# rs232_pic.net
KiCad netlist of a schematic drawn in Altium Designer
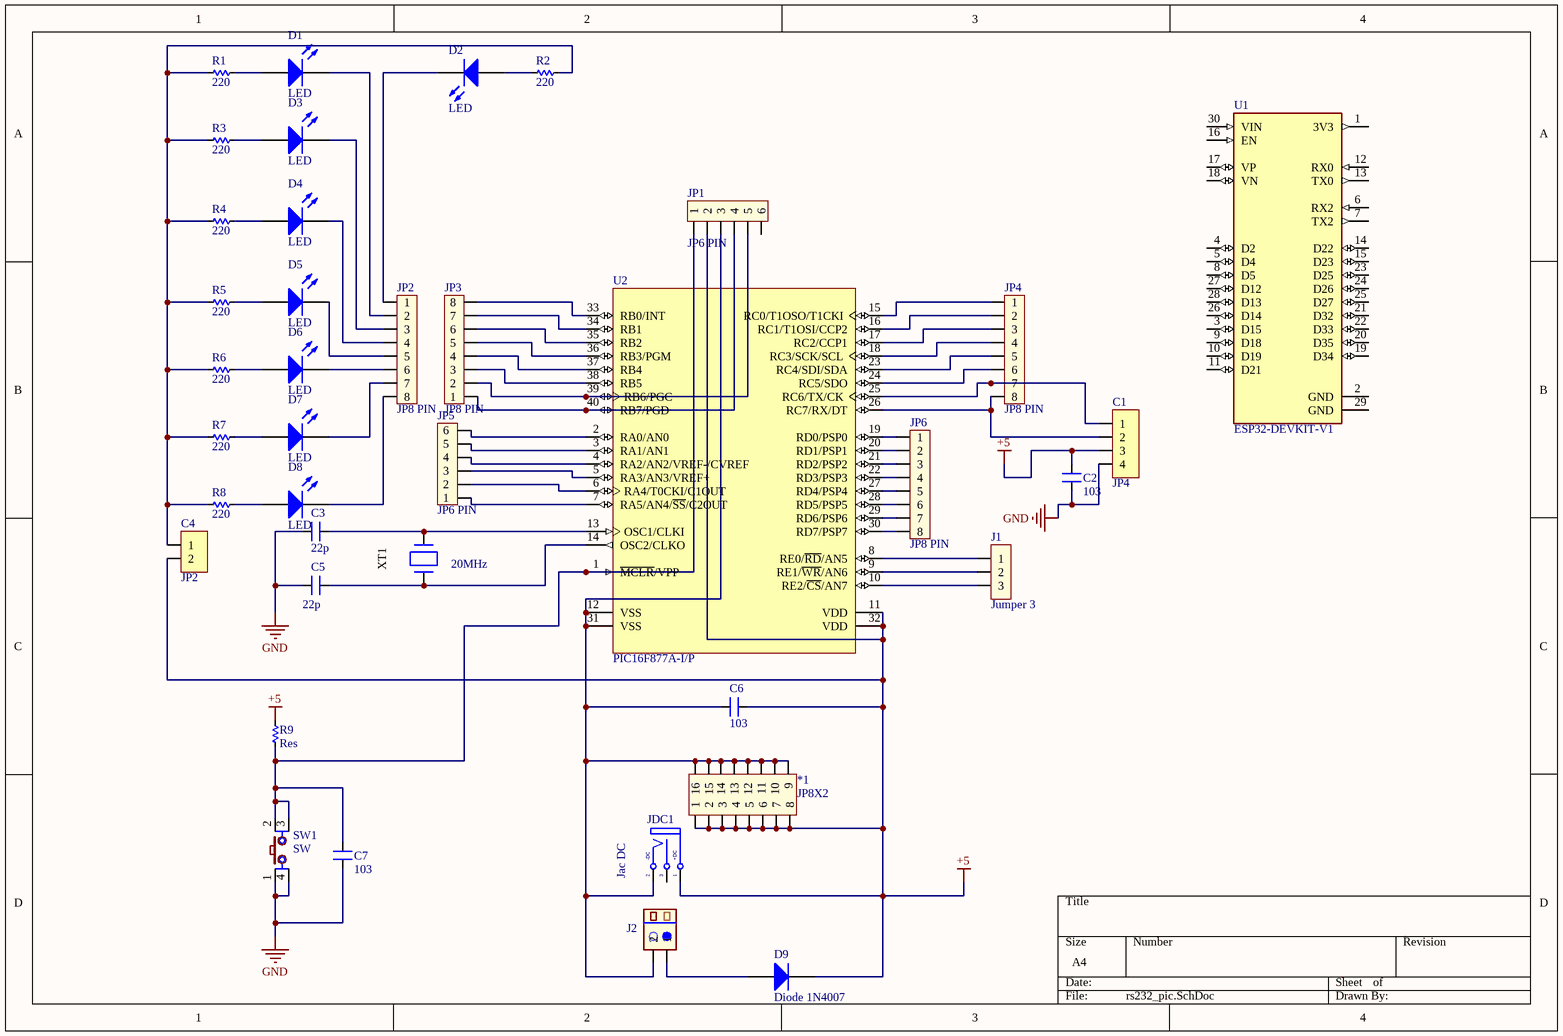
[diagram p0: rs232_pic.SchDoc]

(export (version "E")
  (design (tool "Eeschema 10.0.6"))
  (components
    (comp (ref "*1") (value "JP8X2") (footprint "JP8X2") (libsource (lib "syhaunguyen") (part "JP8X2")))
    (comp (ref "C1")
      (value "JP4")
      (footprint "JP4-C1T")
      (description "WR-PHD 2.54 mm Angled Socket Header")
      (fields
        (field (name "MANUFACTURER") "Würth Elektronik eiSos GmbH")
        (field (name "PARTNO") "613004143121")
        (field (name "CREATED BY") "Karrer Zheng")
      )
      (libsource (lib "LIBRARY1") (part "JP4"))
    )
    (comp (ref "C2")
      (value "103")
      (footprint "CN1.5")
      (description "Cap np 682pF => 104pF")
      (libsource (lib "hphonglib") (part "CN1.5"))
    )
    (comp (ref "C3")
      (value "22p")
      (footprint "CN1.5")
      (description "Cap np 682pF => 104pF")
      (libsource (lib "hphonglib") (part "CN1.5"))
    )
    (comp (ref "C4")
      (value "JP2")
      (footprint "JP2-CLOSED")
      (description "WR-PHD 2.54 mm Angled Socket Header")
      (fields
        (field (name "MANUFACTURER") "Würth Elektronik eiSos GmbH")
        (field (name "PARTNO") "613002143121")
        (field (name "CREATED BY") "Karrer Zheng")
      )
      (libsource (lib "LIBRARY1") (part "JP2"))
    )
    (comp (ref "C5")
      (value "22p")
      (footprint "CN1.5")
      (description "Cap np 682pF => 104pF")
      (libsource (lib "hphonglib") (part "CN1.5"))
    )
    (comp (ref "C6")
      (value "103")
      (footprint "CN1.5")
      (description "Cap np 682pF => 104pF")
      (libsource (lib "hphonglib") (part "CN1.5"))
    )
    (comp (ref "C7")
      (value "103")
      (footprint "CN1.5")
      (description "Cap np 682pF => 104pF")
      (libsource (lib "hphonglib") (part "CN1.5"))
    )
    (comp (ref "D1")
      (value "LED")
      (footprint "LED-0 5mm BLUE")
      (description "Typical LED")
      (fields (field (name "PUBLISHER") "Altium Limited"))
      (libsource (lib "hphonglib") (part "LED"))
    )
    (comp (ref "D2")
      (value "LED")
      (footprint "LED-0 5mm BLUE")
      (description "Typical LED")
      (fields (field (name "PUBLISHER") "Altium Limited"))
      (libsource (lib "hphonglib") (part "LED"))
    )
    (comp (ref "D3")
      (value "LED")
      (footprint "LED-0 5mm BLUE")
      (description "Typical LED")
      (fields (field (name "PUBLISHER") "Altium Limited"))
      (libsource (lib "hphonglib") (part "LED"))
    )
    (comp (ref "D4")
      (value "LED")
      (footprint "LED-0 5mm BLUE")
      (description "Typical LED")
      (fields (field (name "PUBLISHER") "Altium Limited"))
      (libsource (lib "hphonglib") (part "LED"))
    )
    (comp (ref "D5")
      (value "LED")
      (footprint "LED-0 5mm BLUE")
      (description "Typical LED")
      (fields (field (name "PUBLISHER") "Altium Limited"))
      (libsource (lib "hphonglib") (part "LED"))
    )
    (comp (ref "D6")
      (value "LED")
      (footprint "LED-0 5mm BLUE")
      (description "Typical LED")
      (fields (field (name "PUBLISHER") "Altium Limited"))
      (libsource (lib "hphonglib") (part "LED"))
    )
    (comp (ref "D7")
      (value "LED")
      (footprint "LED-0 5mm BLUE")
      (description "Typical LED")
      (fields (field (name "PUBLISHER") "Altium Limited"))
      (libsource (lib "hphonglib") (part "LED"))
    )
    (comp (ref "D8")
      (value "LED")
      (footprint "LED-0 5mm BLUE")
      (description "Typical LED")
      (fields (field (name "PUBLISHER") "Altium Limited"))
      (libsource (lib "hphonglib") (part "LED"))
    )
    (comp (ref "D9")
      (value "Diode 1N4007")
      (footprint "DO-41")
      (description "1 Amp General Purpose Rectifier")
      (fields (field (name "PUBLISHER") "Altium Limited"))
      (libsource (lib "hphonglib") (part "Diode 1N4007"))
    )
    (comp (ref "J1") (value "Jumper 3") (footprint "JP3") (libsource (lib "hphonglib") (part "JP3")))
    (comp (ref "J2")
      (value "CON.Domino2")
      (footprint "Domino 2M")
      (description "2 pins Domino Header")
      (fields (field (name "PUBLISHER") "Hoang Nguyen"))
      (libsource (lib "hphonglib") (part "CON.Domino2"))
    )
    (comp (ref "JDC1")
      (value "Jac DC")
      (footprint "DC0")
      (description "Jac DC input")
      (libsource (lib "LIBRARY1") (part "DCIN"))
    )
    (comp (ref "JP1") (value "JP6 PIN") (footprint "JP6") (libsource (lib "syhaunguyen") (part "JP6")))
    (comp (ref "JP2") (value "JP8 PIN") (footprint "JP8") (libsource (lib "hphonglib") (part "JP8")))
    (comp (ref "JP3") (value "JP8 PIN") (footprint "JP8") (libsource (lib "") (part "JP8_1")))
    (comp (ref "JP4") (value "JP8 PIN") (footprint "JP8") (libsource (lib "hphonglib") (part "JP8")))
    (comp (ref "JP5") (value "JP6 PIN") (footprint "JP6") (libsource (lib "hphonglib") (part "JP6")))
    (comp (ref "JP6") (value "JP8 PIN") (footprint "JP8") (libsource (lib "hphonglib") (part "JP8")))
    (comp (ref "R1")
      (value "220")
      (footprint "RES-1/2W")
      (description "Res")
      (fields
        (field (name "MANUFACTURER") "Generic Components")
        (field (name "PUBLISHER") "Altium Hobart Technology Centre")
      )
      (libsource (lib "LIBRARY1") (part "Res"))
    )
    (comp (ref "R2")
      (value "220")
      (footprint "RES-1/2W")
      (description "Res")
      (fields
        (field (name "MANUFACTURER") "Generic Components")
        (field (name "PUBLISHER") "Altium Hobart Technology Centre")
      )
      (libsource (lib "LIBRARY1") (part "Res"))
    )
    (comp (ref "R3")
      (value "220")
      (footprint "RES-1/2W")
      (description "Res")
      (fields
        (field (name "MANUFACTURER") "Generic Components")
        (field (name "PUBLISHER") "Altium Hobart Technology Centre")
      )
      (libsource (lib "LIBRARY1") (part "Res"))
    )
    (comp (ref "R4")
      (value "220")
      (footprint "RES-1/2W")
      (description "Res")
      (fields
        (field (name "MANUFACTURER") "Generic Components")
        (field (name "PUBLISHER") "Altium Hobart Technology Centre")
      )
      (libsource (lib "LIBRARY1") (part "Res"))
    )
    (comp (ref "R5")
      (value "220")
      (footprint "RES-1/2W")
      (description "Res")
      (fields
        (field (name "MANUFACTURER") "Generic Components")
        (field (name "PUBLISHER") "Altium Hobart Technology Centre")
      )
      (libsource (lib "LIBRARY1") (part "Res"))
    )
    (comp (ref "R6")
      (value "220")
      (footprint "RES-1/2W")
      (description "Res")
      (fields
        (field (name "MANUFACTURER") "Generic Components")
        (field (name "PUBLISHER") "Altium Hobart Technology Centre")
      )
      (libsource (lib "LIBRARY1") (part "Res"))
    )
    (comp (ref "R7")
      (value "220")
      (footprint "RES-1/2W")
      (description "Res")
      (fields
        (field (name "MANUFACTURER") "Generic Components")
        (field (name "PUBLISHER") "Altium Hobart Technology Centre")
      )
      (libsource (lib "LIBRARY1") (part "Res"))
    )
    (comp (ref "R8")
      (value "220")
      (footprint "RES-1/2W")
      (description "Res")
      (fields
        (field (name "MANUFACTURER") "Generic Components")
        (field (name "PUBLISHER") "Altium Hobart Technology Centre")
      )
      (libsource (lib "LIBRARY1") (part "Res"))
    )
    (comp (ref "R9")
      (value "Res")
      (footprint "RES-1/2W")
      (fields
        (field (name "MANUFACTURER") "Generic Components")
        (field (name "PUBLISHER") "Altium Hobart Technology Centre")
      )
      (libsource (lib "LIBRARY1") (part "Res"))
    )
    (comp (ref "SW1")
      (value "SW")
      (footprint "SW2-DIP")
      (description "Switch button 4 pin")
      (libsource (lib "LIBRARY1") (part "SW4"))
    )
    (comp (ref "U1")
      (value "ESP32-DEVKIT-V1")
      (footprint "MODULE_ESP32_DEVKIT_V1")
      (fields (field (name "MF") "Do it"))
      (libsource (lib "ESP32-DEVKIT-V1") (part "ESP32-DEVKIT-V1"))
    )
    (comp (ref "U2")
      (value "PIC16F877A-I/P")
      (footprint "DIP-40")
      (fields (field (name "PUBLISHER") "Altium Limited"))
      (libsource (lib "hphonglib") (part "PIC16F877A-I/P"))
    )
    (comp (ref "XT1")
      (value "20MHz")
      (footprint "Crystal.HC49_N")
      (description "Quarz Crystal")
      (fields (field (name "Comment") "Crystal2") (field (name "PUBLISHER") "Hoang Nguyen"))
      (libsource (lib "hphonglib") (part "Crystal2"))
    )
  )
  (nets
    (net (code "1") (name "+5") (class "Default")
      (node (ref "*1") (pin "1") (pinfunction "1_1") (pintype "passive"))
      (node (ref "*1") (pin "2") (pinfunction "2_2") (pintype "passive"))
      (node (ref "*1") (pin "3") (pinfunction "3_3") (pintype "passive"))
      (node (ref "*1") (pin "4") (pinfunction "4_4") (pintype "passive"))
      (node (ref "*1") (pin "5") (pinfunction "5_5") (pintype "passive"))
      (node (ref "*1") (pin "6") (pinfunction "6_6") (pintype "passive"))
      (node (ref "*1") (pin "7") (pinfunction "7_7") (pintype "passive"))
      (node (ref "*1") (pin "8") (pinfunction "8_8") (pintype "passive"))
      (node (ref "C1") (pin "3") (pinfunction "3_3") (pintype "passive"))
      (node (ref "C2") (pin "1") (pinfunction "1_1") (pintype "passive"))
      (node (ref "C4") (pin "2") (pinfunction "2_2") (pintype "passive"))
      (node (ref "C6") (pin "2") (pinfunction "2_2") (pintype "passive"))
      (node (ref "D9") (pin "2") (pinfunction "K_2") (pintype "passive"))
      (node (ref "JDC1") (pin "1") (pinfunction "T_1") (pintype "passive"))
      (node (ref "JP1") (pin "2") (pinfunction "2_2") (pintype "passive"))
      (node (ref "R9") (pin "1") (pinfunction "1_1") (pintype "passive"))
      (node (ref "U2") (pin "11") (pinfunction "VDD_11") (pintype "power_in"))
      (node (ref "U2") (pin "32") (pinfunction "VDD_32") (pintype "power_in"))
    )
    (net (code "2") (name "GND") (class "Default")
      (node (ref "C1") (pin "4") (pinfunction "4_4") (pintype "passive"))
      (node (ref "C2") (pin "2") (pinfunction "2_2") (pintype "passive"))
      (node (ref "C3") (pin "1") (pinfunction "1_1") (pintype "passive"))
      (node (ref "C5") (pin "1") (pinfunction "1_1") (pintype "passive"))
      (node (ref "C7") (pin "2") (pinfunction "2_2") (pintype "passive"))
      (node (ref "SW1") (pin "1") (pintype "passive"))
      (node (ref "SW1") (pin "4") (pinfunction "4_4") (pintype "passive"))
    )
    (net (code "3") (name "Net-(C4-Pad1)") (class "Default")
      (node (ref "C4") (pin "1") (pinfunction "1_1") (pintype "passive"))
      (node (ref "R1") (pin "1") (pinfunction "1_1") (pintype "passive"))
      (node (ref "R2") (pin "1") (pinfunction "1_1") (pintype "passive"))
      (node (ref "R3") (pin "1") (pinfunction "1_1") (pintype "passive"))
      (node (ref "R4") (pin "1") (pinfunction "1_1") (pintype "passive"))
      (node (ref "R5") (pin "1") (pinfunction "1_1") (pintype "passive"))
      (node (ref "R6") (pin "1") (pinfunction "1_1") (pintype "passive"))
      (node (ref "R7") (pin "1") (pinfunction "1_1") (pintype "passive"))
      (node (ref "R8") (pin "1") (pinfunction "1_1") (pintype "passive"))
    )
    (net (code "4") (name "Net-(D1-A)") (class "Default")
      (node (ref "D1") (pin "1") (pinfunction "A_1") (pintype "passive"))
      (node (ref "R1") (pin "2") (pinfunction "2_2") (pintype "passive"))
    )
    (net (code "5") (name "Net-(D1-K)") (class "Default")
      (node (ref "D1") (pin "2") (pinfunction "K_2") (pintype "passive"))
      (node (ref "JP2") (pin "2") (pinfunction "2_2") (pintype "passive"))
    )
    (net (code "6") (name "Net-(D2-A)") (class "Default")
      (node (ref "D2") (pin "1") (pinfunction "A_1") (pintype "passive"))
      (node (ref "R2") (pin "2") (pinfunction "2_2") (pintype "passive"))
    )
    (net (code "7") (name "Net-(D2-K)") (class "Default")
      (node (ref "D2") (pin "2") (pinfunction "K_2") (pintype "passive"))
      (node (ref "JP2") (pin "1") (pinfunction "1_1") (pintype "passive"))
    )
    (net (code "8") (name "Net-(D3-A)") (class "Default")
      (node (ref "D3") (pin "1") (pinfunction "A_1") (pintype "passive"))
      (node (ref "R3") (pin "2") (pinfunction "2_2") (pintype "passive"))
    )
    (net (code "9") (name "Net-(D3-K)") (class "Default")
      (node (ref "D3") (pin "2") (pinfunction "K_2") (pintype "passive"))
      (node (ref "JP2") (pin "3") (pinfunction "3_3") (pintype "passive"))
    )
    (net (code "10") (name "Net-(D4-A)") (class "Default")
      (node (ref "D4") (pin "1") (pinfunction "A_1") (pintype "passive"))
      (node (ref "R4") (pin "2") (pinfunction "2_2") (pintype "passive"))
    )
    (net (code "11") (name "Net-(D4-K)") (class "Default")
      (node (ref "D4") (pin "2") (pinfunction "K_2") (pintype "passive"))
      (node (ref "JP2") (pin "4") (pinfunction "4_4") (pintype "passive"))
    )
    (net (code "12") (name "Net-(D5-A)") (class "Default")
      (node (ref "D5") (pin "1") (pinfunction "A_1") (pintype "passive"))
      (node (ref "R5") (pin "2") (pinfunction "2_2") (pintype "passive"))
    )
    (net (code "13") (name "Net-(D5-K)") (class "Default")
      (node (ref "D5") (pin "2") (pinfunction "K_2") (pintype "passive"))
      (node (ref "JP2") (pin "5") (pinfunction "5_5") (pintype "passive"))
    )
    (net (code "14") (name "Net-(D6-A)") (class "Default")
      (node (ref "D6") (pin "1") (pinfunction "A_1") (pintype "passive"))
      (node (ref "R6") (pin "2") (pinfunction "2_2") (pintype "passive"))
    )
    (net (code "15") (name "Net-(D6-K)") (class "Default")
      (node (ref "D6") (pin "2") (pinfunction "K_2") (pintype "passive"))
      (node (ref "JP2") (pin "6") (pinfunction "6_6") (pintype "passive"))
    )
    (net (code "16") (name "Net-(D7-A)") (class "Default")
      (node (ref "D7") (pin "1") (pinfunction "A_1") (pintype "passive"))
      (node (ref "R7") (pin "2") (pinfunction "2_2") (pintype "passive"))
    )
    (net (code "17") (name "Net-(D7-K)") (class "Default")
      (node (ref "D7") (pin "2") (pinfunction "K_2") (pintype "passive"))
      (node (ref "JP2") (pin "7") (pinfunction "7_7") (pintype "passive"))
    )
    (net (code "18") (name "Net-(D8-A)") (class "Default")
      (node (ref "D8") (pin "1") (pinfunction "A_1") (pintype "passive"))
      (node (ref "R8") (pin "2") (pinfunction "2_2") (pintype "passive"))
    )
    (net (code "19") (name "Net-(D8-K)") (class "Default")
      (node (ref "D8") (pin "2") (pinfunction "K_2") (pintype "passive"))
      (node (ref "JP2") (pin "8") (pinfunction "8_8") (pintype "passive"))
    )
    (net (code "20") (name "Net-(D9-A)") (class "Default")
      (node (ref "D9") (pin "1") (pinfunction "A_1") (pintype "passive"))
      (node (ref "J2") (pin "1") (pinfunction "1_1") (pintype "passive"))
    )
    (net (code "21") (name "Net-(JDC1-TN)") (class "Default")
      (node (ref "*1") (pin "10") (pinfunction "10_10") (pintype "passive"))
      (node (ref "*1") (pin "11") (pinfunction "11_11") (pintype "passive"))
      (node (ref "*1") (pin "12") (pinfunction "12_12") (pintype "passive"))
      (node (ref "*1") (pin "13") (pinfunction "13_13") (pintype "passive"))
      (node (ref "*1") (pin "14") (pinfunction "14_14") (pintype "passive"))
      (node (ref "*1") (pin "15") (pinfunction "15_15") (pintype "passive"))
      (node (ref "*1") (pin "16") (pinfunction "16_16") (pintype "passive"))
      (node (ref "*1") (pin "9") (pinfunction "9_9") (pintype "passive"))
      (node (ref "C6") (pin "1") (pinfunction "1_1") (pintype "passive"))
      (node (ref "J2") (pin "2") (pinfunction "2_2") (pintype "passive"))
      (node (ref "JDC1") (pin "2") (pinfunction "TN_2") (pintype "passive"))
      (node (ref "JP1") (pin "3") (pinfunction "3_3") (pintype "passive"))
      (node (ref "U2") (pin "12") (pinfunction "VSS_12") (pintype "power_in"))
      (node (ref "U2") (pin "31") (pinfunction "VSS_31") (pintype "power_in"))
    )
    (net (code "22") (name "Net-(U2-OSC1{slash}CLKI)") (class "Default")
      (node (ref "C3") (pin "2") (pinfunction "2_2") (pintype "passive"))
      (node (ref "U2") (pin "13") (pinfunction "OSC1/CLKI_13") (pintype "input"))
      (node (ref "XT1") (pin "2") (pinfunction "2_2") (pintype "passive"))
    )
    (net (code "23") (name "Net-(U2-OSC2{slash}CLKO)") (class "Default")
      (node (ref "C5") (pin "2") (pinfunction "2_2") (pintype "passive"))
      (node (ref "U2") (pin "14") (pinfunction "OSC2/CLKO_14") (pintype "output"))
      (node (ref "XT1") (pin "1") (pinfunction "1_1") (pintype "passive"))
    )
    (net (code "24") (name "Net-(U2-RA0{slash}AN0)") (class "Default")
      (node (ref "JP5") (pin "6") (pinfunction "6_6") (pintype "passive"))
      (node (ref "U2") (pin "2") (pinfunction "RA0/AN0_2") (pintype "bidirectional"))
    )
    (net (code "25") (name "Net-(U2-RA1{slash}AN1)") (class "Default")
      (node (ref "JP5") (pin "5") (pinfunction "5_5") (pintype "passive"))
      (node (ref "U2") (pin "3") (pinfunction "RA1/AN1_3") (pintype "bidirectional"))
    )
    (net (code "26") (name "Net-(U2-RA2{slash}AN2{slash}VREF-{slash}CVREF)") (class "Default")
      (node (ref "JP5") (pin "4") (pinfunction "4_4") (pintype "passive"))
      (node (ref "U2") (pin "4") (pinfunction "RA2/AN2/VREF-/CVREF_4") (pintype "bidirectional"))
    )
    (net (code "27") (name "Net-(U2-RA3{slash}AN3{slash}VREF+)") (class "Default")
      (node (ref "JP5") (pin "3") (pinfunction "3_3") (pintype "passive"))
      (node (ref "U2") (pin "5") (pinfunction "RA3/AN3/VREF+_5") (pintype "bidirectional"))
    )
    (net (code "28") (name "Net-(U2-RA4{slash}T0CKI{slash}C1OUT)") (class "Default")
      (node (ref "JP5") (pin "2") (pinfunction "2_2") (pintype "passive"))
      (node (ref "U2") (pin "6") (pinfunction "RA4/T0CKI/C1OUT_6") (pintype "bidirectional"))
    )
    (net (code "29") (name "Net-(U2-RA5{slash}AN4{slash}~{SS}{slash}C2OUT)") (class "Default")
      (node (ref "JP5") (pin "1") (pinfunction "1_1") (pintype "passive"))
      (node (ref "U2") (pin "7") (pinfunction "RA5/AN4/~{SS}/C2OUT_7") (pintype "bidirectional"))
    )
    (net (code "30") (name "Net-(U2-RB0{slash}INT)") (class "Default")
      (node (ref "JP3") (pin "8") (pinfunction "8_8") (pintype "passive"))
      (node (ref "U2") (pin "33") (pinfunction "RB0/INT_33") (pintype "bidirectional"))
    )
    (net (code "31") (name "Net-(U2-RB1)") (class "Default")
      (node (ref "JP3") (pin "7") (pinfunction "7_7") (pintype "passive"))
      (node (ref "U2") (pin "34") (pinfunction "RB1_34") (pintype "bidirectional"))
    )
    (net (code "32") (name "Net-(U2-RB2)") (class "Default")
      (node (ref "JP3") (pin "6") (pinfunction "6_6") (pintype "passive"))
      (node (ref "U2") (pin "35") (pinfunction "RB2_35") (pintype "bidirectional"))
    )
    (net (code "33") (name "Net-(U2-RB3{slash}PGM)") (class "Default")
      (node (ref "JP3") (pin "5") (pinfunction "5_5") (pintype "passive"))
      (node (ref "U2") (pin "36") (pinfunction "RB3/PGM_36") (pintype "bidirectional"))
    )
    (net (code "34") (name "Net-(U2-RB4)") (class "Default")
      (node (ref "JP3") (pin "4") (pinfunction "4_4") (pintype "passive"))
      (node (ref "U2") (pin "37") (pinfunction "RB4_37") (pintype "bidirectional"))
    )
    (net (code "35") (name "Net-(U2-RB5)") (class "Default")
      (node (ref "JP3") (pin "3") (pinfunction "3_3") (pintype "passive"))
      (node (ref "U2") (pin "38") (pinfunction "RB5_38") (pintype "bidirectional"))
    )
    (net (code "36") (name "Net-(U2-RB6{slash}PGC)") (class "Default")
      (node (ref "JP1") (pin "5") (pinfunction "5_5") (pintype "passive"))
      (node (ref "JP3") (pin "2") (pinfunction "2_2") (pintype "passive"))
      (node (ref "U2") (pin "39") (pinfunction "RB6/PGC_39") (pintype "bidirectional"))
    )
    (net (code "37") (name "Net-(U2-RB7{slash}PGD)") (class "Default")
      (node (ref "JP1") (pin "4") (pinfunction "4_4") (pintype "passive"))
      (node (ref "JP3") (pin "1") (pinfunction "1_1") (pintype "passive"))
      (node (ref "U2") (pin "40") (pinfunction "RB7/PGD_40") (pintype "bidirectional"))
    )
    (net (code "38") (name "Net-(U2-RC0{slash}T1OSO{slash}T1CKI)") (class "Default")
      (node (ref "JP4") (pin "1") (pinfunction "1_1") (pintype "passive"))
      (node (ref "U2") (pin "15") (pinfunction "RC0/T1OSO/T1CKI_15") (pintype "bidirectional"))
    )
    (net (code "39") (name "Net-(U2-RC1{slash}T1OSI{slash}CCP2)") (class "Default")
      (node (ref "JP4") (pin "2") (pinfunction "2_2") (pintype "passive"))
      (node (ref "U2") (pin "16") (pinfunction "RC1/T1OSI/CCP2_16") (pintype "bidirectional"))
    )
    (net (code "40") (name "Net-(U2-RC2{slash}CCP1)") (class "Default")
      (node (ref "JP4") (pin "3") (pinfunction "3_3") (pintype "passive"))
      (node (ref "U2") (pin "17") (pinfunction "RC2/CCP1_17") (pintype "bidirectional"))
    )
    (net (code "41") (name "Net-(U2-RC3{slash}SCK{slash}SCL)") (class "Default")
      (node (ref "JP4") (pin "4") (pinfunction "4_4") (pintype "passive"))
      (node (ref "U2") (pin "18") (pinfunction "RC3/SCK/SCL_18") (pintype "bidirectional"))
    )
    (net (code "42") (name "Net-(U2-RC4{slash}SDI{slash}SDA)") (class "Default")
      (node (ref "JP4") (pin "5") (pinfunction "5_5") (pintype "passive"))
      (node (ref "U2") (pin "23") (pinfunction "RC4/SDI/SDA_23") (pintype "bidirectional"))
    )
    (net (code "43") (name "Net-(U2-RC5{slash}SDO)") (class "Default")
      (node (ref "JP4") (pin "6") (pinfunction "6_6") (pintype "passive"))
      (node (ref "U2") (pin "24") (pinfunction "RC5/SDO_24") (pintype "bidirectional"))
    )
    (net (code "44") (name "Net-(U2-RC6{slash}TX{slash}CK)") (class "Default")
      (node (ref "C1") (pin "1") (pinfunction "1_1") (pintype "passive"))
      (node (ref "JP4") (pin "7") (pinfunction "7_7") (pintype "passive"))
      (node (ref "U2") (pin "25") (pinfunction "RC6/TX/CK_25") (pintype "bidirectional"))
    )
    (net (code "45") (name "Net-(U2-RC7{slash}RX{slash}DT)") (class "Default")
      (node (ref "C1") (pin "2") (pinfunction "2_2") (pintype "passive"))
      (node (ref "JP4") (pin "8") (pinfunction "8_8") (pintype "passive"))
      (node (ref "U2") (pin "26") (pinfunction "RC7/RX/DT_26") (pintype "bidirectional"))
    )
    (net (code "46") (name "Net-(U2-RD0{slash}PSP0)") (class "Default")
      (node (ref "JP6") (pin "1") (pinfunction "1_1") (pintype "passive"))
      (node (ref "U2") (pin "19") (pinfunction "RD0/PSP0_19") (pintype "bidirectional"))
    )
    (net (code "47") (name "Net-(U2-RD1{slash}PSP1)") (class "Default")
      (node (ref "JP6") (pin "2") (pinfunction "2_2") (pintype "passive"))
      (node (ref "U2") (pin "20") (pinfunction "RD1/PSP1_20") (pintype "bidirectional"))
    )
    (net (code "48") (name "Net-(U2-RD2{slash}PSP2)") (class "Default")
      (node (ref "JP6") (pin "3") (pinfunction "3_3") (pintype "passive"))
      (node (ref "U2") (pin "21") (pinfunction "RD2/PSP2_21") (pintype "bidirectional"))
    )
    (net (code "49") (name "Net-(U2-RD3{slash}PSP3)") (class "Default")
      (node (ref "JP6") (pin "4") (pinfunction "4_4") (pintype "passive"))
      (node (ref "U2") (pin "22") (pinfunction "RD3/PSP3_22") (pintype "bidirectional"))
    )
    (net (code "50") (name "Net-(U2-RD4{slash}PSP4)") (class "Default")
      (node (ref "JP6") (pin "5") (pinfunction "5_5") (pintype "passive"))
      (node (ref "U2") (pin "27") (pinfunction "RD4/PSP4_27") (pintype "bidirectional"))
    )
    (net (code "51") (name "Net-(U2-RD5{slash}PSP5)") (class "Default")
      (node (ref "JP6") (pin "6") (pinfunction "6_6") (pintype "passive"))
      (node (ref "U2") (pin "28") (pinfunction "RD5/PSP5_28") (pintype "bidirectional"))
    )
    (net (code "52") (name "Net-(U2-RD6{slash}PSP6)") (class "Default")
      (node (ref "JP6") (pin "7") (pinfunction "7_7") (pintype "passive"))
      (node (ref "U2") (pin "29") (pinfunction "RD6/PSP6_29") (pintype "bidirectional"))
    )
    (net (code "53") (name "Net-(U2-RD7{slash}PSP7)") (class "Default")
      (node (ref "JP6") (pin "8") (pinfunction "8_8") (pintype "passive"))
      (node (ref "U2") (pin "30") (pinfunction "RD7/PSP7_30") (pintype "bidirectional"))
    )
    (net (code "54") (name "Net-(U2-RE0{slash}~{RD}{slash}AN5)") (class "Default")
      (node (ref "J1") (pin "1") (pinfunction "1_1") (pintype "passive"))
      (node (ref "U2") (pin "8") (pinfunction "RE0/~{RD}/AN5_8") (pintype "bidirectional"))
    )
    (net (code "55") (name "Net-(U2-RE1{slash}~{WR}{slash}AN6)") (class "Default")
      (node (ref "J1") (pin "2") (pinfunction "2_2") (pintype "passive"))
      (node (ref "U2") (pin "9") (pinfunction "RE1/~{WR}/AN6_9") (pintype "bidirectional"))
    )
    (net (code "56") (name "Net-(U2-RE2{slash}~{CS}{slash}AN7)") (class "Default")
      (node (ref "J1") (pin "3") (pinfunction "3_3") (pintype "passive"))
      (node (ref "U2") (pin "10") (pinfunction "RE2/~{CS}/AN7_10") (pintype "bidirectional"))
    )
    (net (code "57") (name "Net-(U2-~{MCLR}{slash}VPP)") (class "Default")
      (node (ref "C7") (pin "1") (pinfunction "1_1") (pintype "passive"))
      (node (ref "JP1") (pin "1") (pinfunction "1_1") (pintype "passive"))
      (node (ref "R9") (pin "2") (pinfunction "2_2") (pintype "passive"))
      (node (ref "SW1") (pin "2") (pinfunction "2_2") (pintype "passive"))
      (node (ref "SW1") (pin "3") (pinfunction "3_3") (pintype "passive"))
      (node (ref "U2") (pin "1") (pinfunction "~{MCLR}/VPP_1") (pintype "input"))
    )
    (net (code "58") (name "unconnected-(JDC1-S-Pad3)") (class "Default")
      (node (ref "JDC1") (pin "3") (pinfunction "S_3") (pintype "power_in"))
    )
    (net (code "59") (name "unconnected-(JP1-Pad6)") (class "Default")
      (node (ref "JP1") (pin "6") (pinfunction "6_6") (pintype "passive"))
    )
    (net (code "60") (name "unconnected-(U1-3V3-Pad1)") (class "Default")
      (node (ref "U1") (pin "1") (pinfunction "3V3_1") (pintype "output"))
    )
    (net (code "61") (name "unconnected-(U1-D2-Pad4)") (class "Default")
      (node (ref "U1") (pin "4") (pinfunction "D2_4") (pintype "bidirectional"))
    )
    (net (code "62") (name "unconnected-(U1-D4-Pad5)") (class "Default")
      (node (ref "U1") (pin "5") (pinfunction "D4_5") (pintype "bidirectional"))
    )
    (net (code "63") (name "unconnected-(U1-D5-Pad8)") (class "Default")
      (node (ref "U1") (pin "8") (pinfunction "D5_8") (pintype "bidirectional"))
    )
    (net (code "64") (name "unconnected-(U1-D12-Pad27)") (class "Default")
      (node (ref "U1") (pin "27") (pinfunction "D12_27") (pintype "bidirectional"))
    )
    (net (code "65") (name "unconnected-(U1-D13-Pad28)") (class "Default")
      (node (ref "U1") (pin "28") (pinfunction "D13_28") (pintype "bidirectional"))
    )
    (net (code "66") (name "unconnected-(U1-D14-Pad26)") (class "Default")
      (node (ref "U1") (pin "26") (pinfunction "D14_26") (pintype "bidirectional"))
    )
    (net (code "67") (name "unconnected-(U1-D15-Pad3)") (class "Default")
      (node (ref "U1") (pin "3") (pinfunction "D15_3") (pintype "bidirectional"))
    )
    (net (code "68") (name "unconnected-(U1-D18-Pad9)") (class "Default")
      (node (ref "U1") (pin "9") (pinfunction "D18_9") (pintype "bidirectional"))
    )
    (net (code "69") (name "unconnected-(U1-D19-Pad10)") (class "Default")
      (node (ref "U1") (pin "10") (pinfunction "D19_10") (pintype "bidirectional"))
    )
    (net (code "70") (name "unconnected-(U1-D21-Pad11)") (class "Default")
      (node (ref "U1") (pin "11") (pinfunction "D21_11") (pintype "bidirectional"))
    )
    (net (code "71") (name "unconnected-(U1-D22-Pad14)") (class "Default")
      (node (ref "U1") (pin "14") (pinfunction "D22_14") (pintype "bidirectional"))
    )
    (net (code "72") (name "unconnected-(U1-D23-Pad15)") (class "Default")
      (node (ref "U1") (pin "15") (pinfunction "D23_15") (pintype "bidirectional"))
    )
    (net (code "73") (name "unconnected-(U1-D25-Pad23)") (class "Default")
      (node (ref "U1") (pin "23") (pinfunction "D25_23") (pintype "bidirectional"))
    )
    (net (code "74") (name "unconnected-(U1-D26-Pad24)") (class "Default")
      (node (ref "U1") (pin "24") (pinfunction "D26_24") (pintype "bidirectional"))
    )
    (net (code "75") (name "unconnected-(U1-D27-Pad25)") (class "Default")
      (node (ref "U1") (pin "25") (pinfunction "D27_25") (pintype "bidirectional"))
    )
    (net (code "76") (name "unconnected-(U1-D32-Pad21)") (class "Default")
      (node (ref "U1") (pin "21") (pinfunction "D32_21") (pintype "bidirectional"))
    )
    (net (code "77") (name "unconnected-(U1-D33-Pad22)") (class "Default")
      (node (ref "U1") (pin "22") (pinfunction "D33_22") (pintype "bidirectional"))
    )
    (net (code "78") (name "unconnected-(U1-D34-Pad19)") (class "Default")
      (node (ref "U1") (pin "19") (pinfunction "D34_19") (pintype "bidirectional"))
    )
    (net (code "79") (name "unconnected-(U1-D35-Pad20)") (class "Default")
      (node (ref "U1") (pin "20") (pinfunction "D35_20") (pintype "bidirectional"))
    )
    (net (code "80") (name "unconnected-(U1-EN-Pad16)") (class "Default")
      (node (ref "U1") (pin "16") (pinfunction "EN_16") (pintype "input"))
    )
    (net (code "81") (name "unconnected-(U1-GND-Pad2)") (class "Default")
      (node (ref "U1") (pin "2") (pinfunction "GND_2") (pintype "power_in"))
    )
    (net (code "82") (name "unconnected-(U1-GND-Pad29)") (class "Default")
      (node (ref "U1") (pin "29") (pinfunction "GND_29") (pintype "power_in"))
    )
    (net (code "83") (name "unconnected-(U1-RX0-Pad12)") (class "Default")
      (node (ref "U1") (pin "12") (pinfunction "RX0_12") (pintype "input"))
    )
    (net (code "84") (name "unconnected-(U1-RX2-Pad6)") (class "Default")
      (node (ref "U1") (pin "6") (pinfunction "RX2_6") (pintype "input"))
    )
    (net (code "85") (name "unconnected-(U1-TX0-Pad13)") (class "Default")
      (node (ref "U1") (pin "13") (pinfunction "TX0_13") (pintype "output"))
    )
    (net (code "86") (name "unconnected-(U1-TX2-Pad7)") (class "Default")
      (node (ref "U1") (pin "7") (pinfunction "TX2_7") (pintype "output"))
    )
    (net (code "87") (name "unconnected-(U1-VIN-Pad30)") (class "Default")
      (node (ref "U1") (pin "30") (pinfunction "VIN_30") (pintype "input"))
    )
    (net (code "88") (name "unconnected-(U1-VN-Pad18)") (class "Default")
      (node (ref "U1") (pin "18") (pinfunction "VN_18") (pintype "bidirectional"))
    )
    (net (code "89") (name "unconnected-(U1-VP-Pad17)") (class "Default")
      (node (ref "U1") (pin "17") (pinfunction "VP_17") (pintype "bidirectional"))
    )
  )
)
